# IPSv2_0.net
KiCad netlist of a schematic drawn in EAGLE
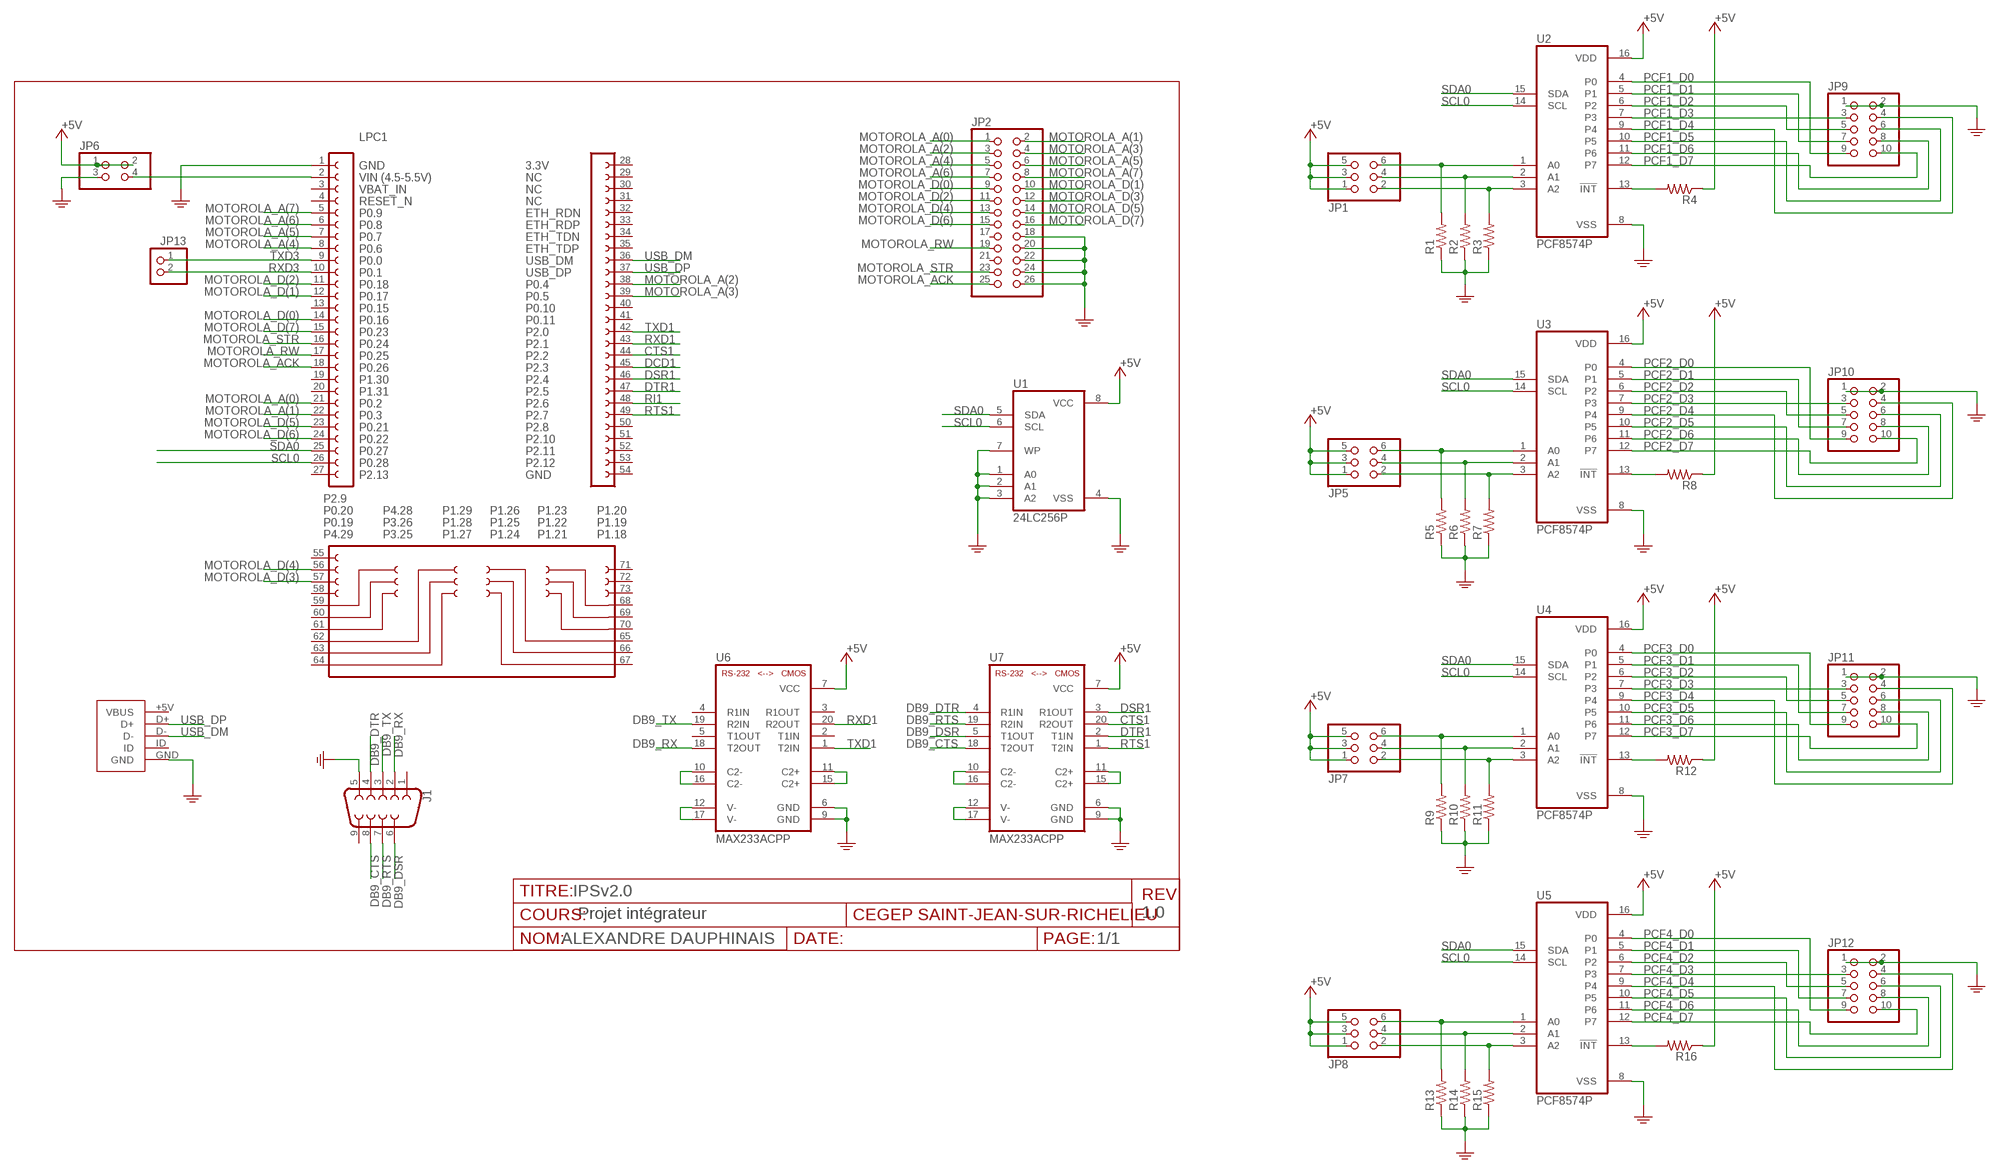
[diagram p0: schematic, sheet 1]

(export (version "E")
  (design (tool "Eeschema 10.0.6"))
  (components
    (comp (ref "J1")
      (value "DB9FEMALE")
      (footprint "eagle-import:DB9")
      (libsource (lib "eagle-import") (part "DB9FEMALE"))
    )
    (comp (ref "JP1")
      (value "PINHD-2X3")
      (footprint "eagle-import:2X03")
      (libsource (lib "eagle-import") (part "PINHD-2X3"))
    )
    (comp (ref "JP2")
      (value "PINHD-2X13")
      (footprint "eagle-import:2X13")
      (libsource (lib "eagle-import") (part "PINHD-2X13"))
    )
    (comp (ref "JP5")
      (value "PINHD-2X3")
      (footprint "eagle-import:2X03")
      (libsource (lib "eagle-import") (part "PINHD-2X3"))
    )
    (comp (ref "JP6")
      (value "PINHD-2X2")
      (footprint "eagle-import:2X02")
      (libsource (lib "eagle-import") (part "PINHD-2X2"))
    )
    (comp (ref "JP7")
      (value "PINHD-2X3")
      (footprint "eagle-import:2X03")
      (libsource (lib "eagle-import") (part "PINHD-2X3"))
    )
    (comp (ref "JP8")
      (value "PINHD-2X3")
      (footprint "eagle-import:2X03")
      (libsource (lib "eagle-import") (part "PINHD-2X3"))
    )
    (comp (ref "JP9")
      (value "PINHD-2X5")
      (footprint "eagle-import:2X05")
      (libsource (lib "eagle-import") (part "PINHD-2X5"))
    )
    (comp (ref "JP10")
      (value "PINHD-2X5")
      (footprint "eagle-import:2X05")
      (libsource (lib "eagle-import") (part "PINHD-2X5"))
    )
    (comp (ref "JP11")
      (value "PINHD-2X5")
      (footprint "eagle-import:2X05")
      (libsource (lib "eagle-import") (part "PINHD-2X5"))
    )
    (comp (ref "JP12")
      (value "PINHD-2X5")
      (footprint "eagle-import:2X05")
      (libsource (lib "eagle-import") (part "PINHD-2X5"))
    )
    (comp (ref "JP13")
      (value "PINHD-1X2")
      (footprint "eagle-import:1X02")
      (libsource (lib "eagle-import") (part "PINHD-1X2"))
    )
    (comp (ref "LPC1")
      (value "LPCXPRESSO_LPC1769")
      (footprint "eagle-import:LPCXPRESSO_LPC1769")
      (libsource (lib "eagle-import") (part "LPCXPRESSO_LPC1769"))
    )
    (comp (ref "R1")
      (value "R-US_M1206")
      (footprint "eagle-import:M1206")
      (libsource (lib "eagle-import") (part "R-US_M1206"))
    )
    (comp (ref "R2")
      (value "R-US_M1206")
      (footprint "eagle-import:M1206")
      (libsource (lib "eagle-import") (part "R-US_M1206"))
    )
    (comp (ref "R3")
      (value "R-US_M1206")
      (footprint "eagle-import:M1206")
      (libsource (lib "eagle-import") (part "R-US_M1206"))
    )
    (comp (ref "R4")
      (value "R-US_M1206")
      (footprint "eagle-import:M1206")
      (libsource (lib "eagle-import") (part "R-US_M1206"))
    )
    (comp (ref "R5")
      (value "R-US_M1206")
      (footprint "eagle-import:M1206")
      (libsource (lib "eagle-import") (part "R-US_M1206"))
    )
    (comp (ref "R6")
      (value "R-US_M1206")
      (footprint "eagle-import:M1206")
      (libsource (lib "eagle-import") (part "R-US_M1206"))
    )
    (comp (ref "R7")
      (value "R-US_M1206")
      (footprint "eagle-import:M1206")
      (libsource (lib "eagle-import") (part "R-US_M1206"))
    )
    (comp (ref "R8")
      (value "R-US_M1206")
      (footprint "eagle-import:M1206")
      (libsource (lib "eagle-import") (part "R-US_M1206"))
    )
    (comp (ref "R9")
      (value "R-US_M1206")
      (footprint "eagle-import:M1206")
      (libsource (lib "eagle-import") (part "R-US_M1206"))
    )
    (comp (ref "R10")
      (value "R-US_M1206")
      (footprint "eagle-import:M1206")
      (libsource (lib "eagle-import") (part "R-US_M1206"))
    )
    (comp (ref "R11")
      (value "R-US_M1206")
      (footprint "eagle-import:M1206")
      (libsource (lib "eagle-import") (part "R-US_M1206"))
    )
    (comp (ref "R12")
      (value "R-US_M1206")
      (footprint "eagle-import:M1206")
      (libsource (lib "eagle-import") (part "R-US_M1206"))
    )
    (comp (ref "R13")
      (value "R-US_M1206")
      (footprint "eagle-import:M1206")
      (libsource (lib "eagle-import") (part "R-US_M1206"))
    )
    (comp (ref "R14")
      (value "R-US_M1206")
      (footprint "eagle-import:M1206")
      (libsource (lib "eagle-import") (part "R-US_M1206"))
    )
    (comp (ref "R15")
      (value "R-US_M1206")
      (footprint "eagle-import:M1206")
      (libsource (lib "eagle-import") (part "R-US_M1206"))
    )
    (comp (ref "R16")
      (value "R-US_M1206")
      (footprint "eagle-import:M1206")
      (libsource (lib "eagle-import") (part "R-US_M1206"))
    )
    (comp (ref "U$2")
      (value "USB-MICRO-BREAKOUT")
      (footprint "eagle-import:USB-MICRO-BREAKOUT")
      (libsource (lib "eagle-import") (part "USB-MICRO-BREAKOUT"))
    )
    (comp (ref "U1")
      (value "24LC256P")
      (footprint "eagle-import:DIP08")
      (libsource (lib "eagle-import") (part "24LC256P"))
    )
    (comp (ref "U2")
      (value "PCF8574P")
      (footprint "eagle-import:DIP16")
      (libsource (lib "eagle-import") (part "PCF8574P"))
    )
    (comp (ref "U3")
      (value "PCF8574P")
      (footprint "eagle-import:DIP16")
      (libsource (lib "eagle-import") (part "PCF8574P"))
    )
    (comp (ref "U4")
      (value "PCF8574P")
      (footprint "eagle-import:DIP16")
      (libsource (lib "eagle-import") (part "PCF8574P"))
    )
    (comp (ref "U5")
      (value "PCF8574P")
      (footprint "eagle-import:DIP16")
      (libsource (lib "eagle-import") (part "PCF8574P"))
    )
    (comp (ref "U6")
      (value "MAX233ACPP")
      (footprint "eagle-import:DIP20")
      (libsource (lib "eagle-import") (part "MAX233ACPP"))
    )
    (comp (ref "U7")
      (value "MAX233ACPP")
      (footprint "eagle-import:DIP20")
      (libsource (lib "eagle-import") (part "MAX233ACPP"))
    )
  )
  (nets
    (net (code "1") (name "+5V") (class "Default")
      (node (ref "JP1") (pin "1") (pinfunction "1_1") (pintype "passive"))
      (node (ref "JP1") (pin "3") (pinfunction "3_3") (pintype "passive"))
      (node (ref "JP1") (pin "5") (pinfunction "5_5") (pintype "passive"))
      (node (ref "JP5") (pin "1") (pinfunction "1_1") (pintype "passive"))
      (node (ref "JP5") (pin "3") (pinfunction "3_3") (pintype "passive"))
      (node (ref "JP5") (pin "5") (pinfunction "5_5") (pintype "passive"))
      (node (ref "JP6") (pin "1") (pinfunction "1_1") (pintype "passive"))
      (node (ref "JP6") (pin "2") (pinfunction "2_2") (pintype "passive"))
      (node (ref "JP7") (pin "1") (pinfunction "1_1") (pintype "passive"))
      (node (ref "JP7") (pin "3") (pinfunction "3_3") (pintype "passive"))
      (node (ref "JP7") (pin "5") (pinfunction "5_5") (pintype "passive"))
      (node (ref "JP8") (pin "1") (pinfunction "1_1") (pintype "passive"))
      (node (ref "JP8") (pin "3") (pinfunction "3_3") (pintype "passive"))
      (node (ref "JP8") (pin "5") (pinfunction "5_5") (pintype "passive"))
      (node (ref "R12") (pin "1") (pinfunction "1_1") (pintype "passive"))
      (node (ref "R16") (pin "1") (pinfunction "1_1") (pintype "passive"))
      (node (ref "R4") (pin "1") (pinfunction "1_1") (pintype "passive"))
      (node (ref "R8") (pin "1") (pinfunction "1_1") (pintype "passive"))
      (node (ref "U1") (pin "8") (pinfunction "VCC_8") (pintype "power_in"))
      (node (ref "U2") (pin "16") (pinfunction "VDD_16") (pintype "power_in"))
      (node (ref "U3") (pin "16") (pinfunction "VDD_16") (pintype "power_in"))
      (node (ref "U4") (pin "16") (pinfunction "VDD_16") (pintype "power_in"))
      (node (ref "U5") (pin "16") (pinfunction "VDD_16") (pintype "power_in"))
      (node (ref "U6") (pin "7") (pinfunction "VCC_7") (pintype "power_in"))
      (node (ref "U7") (pin "7") (pinfunction "VCC_7") (pintype "power_in"))
    )
    (net (code "2") (name "/CTS1") (class "Default")
      (node (ref "LPC1") (pin "44") (pinfunction "44_44") (pintype "passive"))
      (node (ref "U7") (pin "20") (pinfunction "R2OUT_20") (pintype "output"))
    )
    (net (code "3") (name "/DB9_CTS") (class "Default")
      (node (ref "J1") (pin "8") (pinfunction "8_8") (pintype "passive"))
      (node (ref "U7") (pin "18") (pinfunction "T2OUT_18") (pintype "output"))
    )
    (net (code "4") (name "/DB9_DSR") (class "Default")
      (node (ref "J1") (pin "6") (pinfunction "6_6") (pintype "passive"))
      (node (ref "U7") (pin "5") (pinfunction "T1OUT_5") (pintype "output"))
    )
    (net (code "5") (name "/DB9_DTR") (class "Default")
      (node (ref "J1") (pin "4") (pinfunction "4_4") (pintype "passive"))
      (node (ref "U7") (pin "4") (pinfunction "R1IN_4") (pintype "input"))
    )
    (net (code "6") (name "/DB9_RTS") (class "Default")
      (node (ref "J1") (pin "7") (pinfunction "7_7") (pintype "passive"))
      (node (ref "U7") (pin "19") (pinfunction "R2IN_19") (pintype "input"))
    )
    (net (code "7") (name "/DB9_RX") (class "Default")
      (node (ref "J1") (pin "2") (pinfunction "2_2") (pintype "passive"))
      (node (ref "U6") (pin "18") (pinfunction "T2OUT_18") (pintype "output"))
    )
    (net (code "8") (name "/DB9_TX") (class "Default")
      (node (ref "J1") (pin "3") (pinfunction "3_3") (pintype "passive"))
      (node (ref "U6") (pin "19") (pinfunction "R2IN_19") (pintype "input"))
    )
    (net (code "9") (name "/DCD1") (class "Default")
      (node (ref "LPC1") (pin "45") (pinfunction "45_45") (pintype "passive"))
    )
    (net (code "10") (name "/DSR1") (class "Default")
      (node (ref "LPC1") (pin "46") (pinfunction "46_46") (pintype "passive"))
      (node (ref "U7") (pin "3") (pinfunction "R1OUT_3") (pintype "output"))
    )
    (net (code "11") (name "/DTR1") (class "Default")
      (node (ref "LPC1") (pin "47") (pinfunction "47_47") (pintype "passive"))
      (node (ref "U7") (pin "2") (pinfunction "T1IN_2") (pintype "input"))
    )
    (net (code "12") (name "/MOTOROLA_A(0)") (class "Default")
      (node (ref "JP2") (pin "1") (pinfunction "1_1") (pintype "passive"))
      (node (ref "LPC1") (pin "21") (pinfunction "21_21") (pintype "passive"))
    )
    (net (code "13") (name "/MOTOROLA_A(1)") (class "Default")
      (node (ref "JP2") (pin "2") (pinfunction "2_2") (pintype "passive"))
      (node (ref "LPC1") (pin "22") (pinfunction "22_22") (pintype "passive"))
    )
    (net (code "14") (name "/MOTOROLA_A(2)") (class "Default")
      (node (ref "JP2") (pin "3") (pinfunction "3_3") (pintype "passive"))
      (node (ref "LPC1") (pin "38") (pinfunction "38_38") (pintype "passive"))
    )
    (net (code "15") (name "/MOTOROLA_A(3)") (class "Default")
      (node (ref "JP2") (pin "4") (pinfunction "4_4") (pintype "passive"))
      (node (ref "LPC1") (pin "39") (pinfunction "39_39") (pintype "passive"))
    )
    (net (code "16") (name "/MOTOROLA_A(4)") (class "Default")
      (node (ref "JP2") (pin "5") (pinfunction "5_5") (pintype "passive"))
      (node (ref "LPC1") (pin "8") (pinfunction "8_8") (pintype "passive"))
    )
    (net (code "17") (name "/MOTOROLA_A(5)") (class "Default")
      (node (ref "JP2") (pin "6") (pinfunction "6_6") (pintype "passive"))
      (node (ref "LPC1") (pin "7") (pinfunction "7_7") (pintype "passive"))
    )
    (net (code "18") (name "/MOTOROLA_A(6)") (class "Default")
      (node (ref "JP2") (pin "7") (pinfunction "7_7") (pintype "passive"))
      (node (ref "LPC1") (pin "6") (pinfunction "6_6") (pintype "passive"))
    )
    (net (code "19") (name "/MOTOROLA_A(7)") (class "Default")
      (node (ref "JP2") (pin "8") (pinfunction "8_8") (pintype "passive"))
      (node (ref "LPC1") (pin "5") (pinfunction "5_5") (pintype "passive"))
    )
    (net (code "20") (name "/MOTOROLA_ACK") (class "Default")
      (node (ref "JP2") (pin "25") (pinfunction "25_25") (pintype "passive"))
      (node (ref "LPC1") (pin "18") (pinfunction "18_18") (pintype "passive"))
    )
    (net (code "21") (name "/MOTOROLA_D(0)") (class "Default")
      (node (ref "JP2") (pin "9") (pinfunction "9_9") (pintype "passive"))
      (node (ref "LPC1") (pin "14") (pinfunction "14_14") (pintype "passive"))
    )
    (net (code "22") (name "/MOTOROLA_D(1)") (class "Default")
      (node (ref "JP2") (pin "10") (pinfunction "10_10") (pintype "passive"))
      (node (ref "LPC1") (pin "12") (pinfunction "12_12") (pintype "passive"))
    )
    (net (code "23") (name "/MOTOROLA_D(2)") (class "Default")
      (node (ref "JP2") (pin "11") (pinfunction "11_11") (pintype "passive"))
      (node (ref "LPC1") (pin "11") (pinfunction "11_11") (pintype "passive"))
    )
    (net (code "24") (name "/MOTOROLA_D(3)") (class "Default")
      (node (ref "JP2") (pin "12") (pinfunction "12_12") (pintype "passive"))
      (node (ref "LPC1") (pin "57") (pinfunction "57_57") (pintype "passive"))
    )
    (net (code "25") (name "/MOTOROLA_D(4)") (class "Default")
      (node (ref "JP2") (pin "13") (pinfunction "13_13") (pintype "passive"))
      (node (ref "LPC1") (pin "56") (pinfunction "56_56") (pintype "passive"))
    )
    (net (code "26") (name "/MOTOROLA_D(5)") (class "Default")
      (node (ref "JP2") (pin "14") (pinfunction "14_14") (pintype "passive"))
      (node (ref "LPC1") (pin "23") (pinfunction "23_23") (pintype "passive"))
    )
    (net (code "27") (name "/MOTOROLA_D(6)") (class "Default")
      (node (ref "JP2") (pin "15") (pinfunction "15_15") (pintype "passive"))
      (node (ref "LPC1") (pin "24") (pinfunction "24_24") (pintype "passive"))
    )
    (net (code "28") (name "/MOTOROLA_D(7)") (class "Default")
      (node (ref "JP2") (pin "16") (pinfunction "16_16") (pintype "passive"))
      (node (ref "LPC1") (pin "15") (pinfunction "15_15") (pintype "passive"))
    )
    (net (code "29") (name "/MOTOROLA_RW") (class "Default")
      (node (ref "JP2") (pin "19") (pinfunction "19_19") (pintype "passive"))
      (node (ref "LPC1") (pin "17") (pinfunction "17_17") (pintype "passive"))
    )
    (net (code "30") (name "/MOTOROLA_STR") (class "Default")
      (node (ref "JP2") (pin "23") (pinfunction "23_23") (pintype "passive"))
      (node (ref "LPC1") (pin "16") (pinfunction "16_16") (pintype "passive"))
    )
    (net (code "31") (name "/PCF1_D0") (class "Default")
      (node (ref "JP9") (pin "9") (pinfunction "9_9") (pintype "passive"))
      (node (ref "U2") (pin "4") (pinfunction "P0_4") (pintype "bidirectional"))
    )
    (net (code "32") (name "/PCF1_D1") (class "Default")
      (node (ref "JP9") (pin "7") (pinfunction "7_7") (pintype "passive"))
      (node (ref "U2") (pin "5") (pinfunction "P1_5") (pintype "bidirectional"))
    )
    (net (code "33") (name "/PCF1_D2") (class "Default")
      (node (ref "JP9") (pin "5") (pinfunction "5_5") (pintype "passive"))
      (node (ref "U2") (pin "6") (pinfunction "P2_6") (pintype "bidirectional"))
    )
    (net (code "34") (name "/PCF1_D3") (class "Default")
      (node (ref "JP9") (pin "3") (pinfunction "3_3") (pintype "passive"))
      (node (ref "U2") (pin "7") (pinfunction "P3_7") (pintype "bidirectional"))
    )
    (net (code "35") (name "/PCF1_D4") (class "Default")
      (node (ref "JP9") (pin "4") (pinfunction "4_4") (pintype "passive"))
      (node (ref "U2") (pin "9") (pinfunction "P4_9") (pintype "bidirectional"))
    )
    (net (code "36") (name "/PCF1_D5") (class "Default")
      (node (ref "JP9") (pin "6") (pinfunction "6_6") (pintype "passive"))
      (node (ref "U2") (pin "10") (pinfunction "P5_10") (pintype "bidirectional"))
    )
    (net (code "37") (name "/PCF1_D6") (class "Default")
      (node (ref "JP9") (pin "8") (pinfunction "8_8") (pintype "passive"))
      (node (ref "U2") (pin "11") (pinfunction "P6_11") (pintype "bidirectional"))
    )
    (net (code "38") (name "/PCF1_D7") (class "Default")
      (node (ref "JP9") (pin "10") (pinfunction "10_10") (pintype "passive"))
      (node (ref "U2") (pin "12") (pinfunction "P7_12") (pintype "bidirectional"))
    )
    (net (code "39") (name "/PCF2_D0") (class "Default")
      (node (ref "JP10") (pin "9") (pinfunction "9_9") (pintype "passive"))
      (node (ref "U3") (pin "4") (pinfunction "P0_4") (pintype "bidirectional"))
    )
    (net (code "40") (name "/PCF2_D1") (class "Default")
      (node (ref "JP10") (pin "7") (pinfunction "7_7") (pintype "passive"))
      (node (ref "U3") (pin "5") (pinfunction "P1_5") (pintype "bidirectional"))
    )
    (net (code "41") (name "/PCF2_D2") (class "Default")
      (node (ref "JP10") (pin "5") (pinfunction "5_5") (pintype "passive"))
      (node (ref "U3") (pin "6") (pinfunction "P2_6") (pintype "bidirectional"))
    )
    (net (code "42") (name "/PCF2_D3") (class "Default")
      (node (ref "JP10") (pin "3") (pinfunction "3_3") (pintype "passive"))
      (node (ref "U3") (pin "7") (pinfunction "P3_7") (pintype "bidirectional"))
    )
    (net (code "43") (name "/PCF2_D4") (class "Default")
      (node (ref "JP10") (pin "4") (pinfunction "4_4") (pintype "passive"))
      (node (ref "U3") (pin "9") (pinfunction "P4_9") (pintype "bidirectional"))
    )
    (net (code "44") (name "/PCF2_D5") (class "Default")
      (node (ref "JP10") (pin "6") (pinfunction "6_6") (pintype "passive"))
      (node (ref "U3") (pin "10") (pinfunction "P5_10") (pintype "bidirectional"))
    )
    (net (code "45") (name "/PCF2_D6") (class "Default")
      (node (ref "JP10") (pin "8") (pinfunction "8_8") (pintype "passive"))
      (node (ref "U3") (pin "11") (pinfunction "P6_11") (pintype "bidirectional"))
    )
    (net (code "46") (name "/PCF2_D7") (class "Default")
      (node (ref "JP10") (pin "10") (pinfunction "10_10") (pintype "passive"))
      (node (ref "U3") (pin "12") (pinfunction "P7_12") (pintype "bidirectional"))
    )
    (net (code "47") (name "/PCF3_D0") (class "Default")
      (node (ref "JP11") (pin "9") (pinfunction "9_9") (pintype "passive"))
      (node (ref "U4") (pin "4") (pinfunction "P0_4") (pintype "bidirectional"))
    )
    (net (code "48") (name "/PCF3_D1") (class "Default")
      (node (ref "JP11") (pin "7") (pinfunction "7_7") (pintype "passive"))
      (node (ref "U4") (pin "5") (pinfunction "P1_5") (pintype "bidirectional"))
    )
    (net (code "49") (name "/PCF3_D2") (class "Default")
      (node (ref "JP11") (pin "5") (pinfunction "5_5") (pintype "passive"))
      (node (ref "U4") (pin "6") (pinfunction "P2_6") (pintype "bidirectional"))
    )
    (net (code "50") (name "/PCF3_D3") (class "Default")
      (node (ref "JP11") (pin "3") (pinfunction "3_3") (pintype "passive"))
      (node (ref "U4") (pin "7") (pinfunction "P3_7") (pintype "bidirectional"))
    )
    (net (code "51") (name "/PCF3_D4") (class "Default")
      (node (ref "JP11") (pin "4") (pinfunction "4_4") (pintype "passive"))
      (node (ref "U4") (pin "9") (pinfunction "P4_9") (pintype "bidirectional"))
    )
    (net (code "52") (name "/PCF3_D5") (class "Default")
      (node (ref "JP11") (pin "6") (pinfunction "6_6") (pintype "passive"))
      (node (ref "U4") (pin "10") (pinfunction "P5_10") (pintype "bidirectional"))
    )
    (net (code "53") (name "/PCF3_D6") (class "Default")
      (node (ref "JP11") (pin "8") (pinfunction "8_8") (pintype "passive"))
      (node (ref "U4") (pin "11") (pinfunction "P6_11") (pintype "bidirectional"))
    )
    (net (code "54") (name "/PCF3_D7") (class "Default")
      (node (ref "JP11") (pin "10") (pinfunction "10_10") (pintype "passive"))
      (node (ref "U4") (pin "12") (pinfunction "P7_12") (pintype "bidirectional"))
    )
    (net (code "55") (name "/PCF4_D0") (class "Default")
      (node (ref "JP12") (pin "9") (pinfunction "9_9") (pintype "passive"))
      (node (ref "U5") (pin "4") (pinfunction "P0_4") (pintype "bidirectional"))
    )
    (net (code "56") (name "/PCF4_D1") (class "Default")
      (node (ref "JP12") (pin "7") (pinfunction "7_7") (pintype "passive"))
      (node (ref "U5") (pin "5") (pinfunction "P1_5") (pintype "bidirectional"))
    )
    (net (code "57") (name "/PCF4_D2") (class "Default")
      (node (ref "JP12") (pin "5") (pinfunction "5_5") (pintype "passive"))
      (node (ref "U5") (pin "6") (pinfunction "P2_6") (pintype "bidirectional"))
    )
    (net (code "58") (name "/PCF4_D3") (class "Default")
      (node (ref "JP12") (pin "3") (pinfunction "3_3") (pintype "passive"))
      (node (ref "U5") (pin "7") (pinfunction "P3_7") (pintype "bidirectional"))
    )
    (net (code "59") (name "/PCF4_D4") (class "Default")
      (node (ref "JP12") (pin "4") (pinfunction "4_4") (pintype "passive"))
      (node (ref "U5") (pin "9") (pinfunction "P4_9") (pintype "bidirectional"))
    )
    (net (code "60") (name "/PCF4_D5") (class "Default")
      (node (ref "JP12") (pin "6") (pinfunction "6_6") (pintype "passive"))
      (node (ref "U5") (pin "10") (pinfunction "P5_10") (pintype "bidirectional"))
    )
    (net (code "61") (name "/PCF4_D6") (class "Default")
      (node (ref "JP12") (pin "8") (pinfunction "8_8") (pintype "passive"))
      (node (ref "U5") (pin "11") (pinfunction "P6_11") (pintype "bidirectional"))
    )
    (net (code "62") (name "/PCF4_D7") (class "Default")
      (node (ref "JP12") (pin "10") (pinfunction "10_10") (pintype "passive"))
      (node (ref "U5") (pin "12") (pinfunction "P7_12") (pintype "bidirectional"))
    )
    (net (code "63") (name "/RI1") (class "Default")
      (node (ref "LPC1") (pin "48") (pinfunction "48_48") (pintype "passive"))
    )
    (net (code "64") (name "/RTS1") (class "Default")
      (node (ref "LPC1") (pin "49") (pinfunction "49_49") (pintype "passive"))
      (node (ref "U7") (pin "1") (pinfunction "T2IN_1") (pintype "input"))
    )
    (net (code "65") (name "/RXD1") (class "Default")
      (node (ref "LPC1") (pin "43") (pinfunction "43_43") (pintype "passive"))
      (node (ref "U6") (pin "20") (pinfunction "R2OUT_20") (pintype "output"))
    )
    (net (code "66") (name "/RXD3") (class "Default")
      (node (ref "JP13") (pin "2") (pinfunction "2_2") (pintype "passive"))
      (node (ref "LPC1") (pin "10") (pinfunction "10_10") (pintype "passive"))
    )
    (net (code "67") (name "/SCL0") (class "Default")
      (node (ref "LPC1") (pin "26") (pinfunction "26_26") (pintype "passive"))
      (node (ref "U1") (pin "6") (pinfunction "SCL_6") (pintype "input"))
      (node (ref "U2") (pin "14") (pinfunction "SCL_14") (pintype "input"))
      (node (ref "U3") (pin "14") (pinfunction "SCL_14") (pintype "input"))
      (node (ref "U4") (pin "14") (pinfunction "SCL_14") (pintype "input"))
      (node (ref "U5") (pin "14") (pinfunction "SCL_14") (pintype "input"))
    )
    (net (code "68") (name "/SDA0") (class "Default")
      (node (ref "LPC1") (pin "25") (pinfunction "25_25") (pintype "passive"))
      (node (ref "U1") (pin "5") (pinfunction "SDA_5") (pintype "bidirectional"))
      (node (ref "U2") (pin "15") (pinfunction "SDA_15") (pintype "bidirectional"))
      (node (ref "U3") (pin "15") (pinfunction "SDA_15") (pintype "bidirectional"))
      (node (ref "U4") (pin "15") (pinfunction "SDA_15") (pintype "bidirectional"))
      (node (ref "U5") (pin "15") (pinfunction "SDA_15") (pintype "bidirectional"))
    )
    (net (code "69") (name "/TXD1") (class "Default")
      (node (ref "LPC1") (pin "42") (pinfunction "42_42") (pintype "passive"))
      (node (ref "U6") (pin "1") (pinfunction "T2IN_1") (pintype "input"))
    )
    (net (code "70") (name "/TXD3") (class "Default")
      (node (ref "JP13") (pin "1") (pinfunction "1_1") (pintype "passive"))
      (node (ref "LPC1") (pin "9") (pinfunction "9_9") (pintype "passive"))
    )
    (net (code "71") (name "/USB_DM") (class "Default")
      (node (ref "LPC1") (pin "36") (pinfunction "36_36") (pintype "passive"))
      (node (ref "U$2") (pin "D-") (pinfunction "D-_D-") (pintype "bidirectional"))
    )
    (net (code "72") (name "/USB_DP") (class "Default")
      (node (ref "LPC1") (pin "37") (pinfunction "37_37") (pintype "passive"))
      (node (ref "U$2") (pin "D+") (pinfunction "D+_D+") (pintype "bidirectional"))
    )
    (net (code "73") (name "/VBUS") (class "Default")
      (node (ref "U$2") (pin "+5V") (pinfunction "VBUS_+5V") (pintype "power_in"))
    )
    (net (code "74") (name "GND") (class "Default")
      (node (ref "J1") (pin "5") (pinfunction "5_5") (pintype "passive"))
      (node (ref "JP10") (pin "1") (pinfunction "1_1") (pintype "passive"))
      (node (ref "JP10") (pin "2") (pinfunction "2_2") (pintype "passive"))
      (node (ref "JP11") (pin "1") (pinfunction "1_1") (pintype "passive"))
      (node (ref "JP11") (pin "2") (pinfunction "2_2") (pintype "passive"))
      (node (ref "JP12") (pin "1") (pinfunction "1_1") (pintype "passive"))
      (node (ref "JP12") (pin "2") (pinfunction "2_2") (pintype "passive"))
      (node (ref "JP2") (pin "18") (pinfunction "18_18") (pintype "passive"))
      (node (ref "JP2") (pin "20") (pinfunction "20_20") (pintype "passive"))
      (node (ref "JP2") (pin "22") (pinfunction "22_22") (pintype "passive"))
      (node (ref "JP2") (pin "24") (pinfunction "24_24") (pintype "passive"))
      (node (ref "JP2") (pin "26") (pinfunction "26_26") (pintype "passive"))
      (node (ref "JP6") (pin "3") (pinfunction "3_3") (pintype "passive"))
      (node (ref "JP9") (pin "1") (pinfunction "1_1") (pintype "passive"))
      (node (ref "JP9") (pin "2") (pinfunction "2_2") (pintype "passive"))
      (node (ref "LPC1") (pin "1") (pinfunction "1_1") (pintype "passive"))
      (node (ref "R1") (pin "1") (pinfunction "1_1") (pintype "passive"))
      (node (ref "R10") (pin "1") (pinfunction "1_1") (pintype "passive"))
      (node (ref "R11") (pin "1") (pinfunction "1_1") (pintype "passive"))
      (node (ref "R13") (pin "1") (pinfunction "1_1") (pintype "passive"))
      (node (ref "R14") (pin "1") (pinfunction "1_1") (pintype "passive"))
      (node (ref "R15") (pin "1") (pinfunction "1_1") (pintype "passive"))
      (node (ref "R2") (pin "1") (pinfunction "1_1") (pintype "passive"))
      (node (ref "R3") (pin "1") (pinfunction "1_1") (pintype "passive"))
      (node (ref "R5") (pin "1") (pinfunction "1_1") (pintype "passive"))
      (node (ref "R6") (pin "1") (pinfunction "1_1") (pintype "passive"))
      (node (ref "R7") (pin "1") (pinfunction "1_1") (pintype "passive"))
      (node (ref "R9") (pin "1") (pinfunction "1_1") (pintype "passive"))
      (node (ref "U$2") (pin "GND") (pinfunction "GND_GND") (pintype "power_in"))
      (node (ref "U1") (pin "1") (pinfunction "A0_1") (pintype "input"))
      (node (ref "U1") (pin "2") (pinfunction "A1_2") (pintype "input"))
      (node (ref "U1") (pin "3") (pinfunction "A2_3") (pintype "input"))
      (node (ref "U1") (pin "4") (pinfunction "VSS_4") (pintype "power_in"))
      (node (ref "U1") (pin "7") (pinfunction "WP_7") (pintype "input"))
      (node (ref "U2") (pin "8") (pinfunction "VSS_8") (pintype "power_in"))
      (node (ref "U3") (pin "8") (pinfunction "VSS_8") (pintype "power_in"))
      (node (ref "U4") (pin "8") (pinfunction "VSS_8") (pintype "power_in"))
      (node (ref "U5") (pin "8") (pinfunction "VSS_8") (pintype "power_in"))
      (node (ref "U6") (pin "6") (pinfunction "GND_6") (pintype "power_in"))
      (node (ref "U6") (pin "9") (pinfunction "GND_9") (pintype "power_in"))
      (node (ref "U7") (pin "6") (pinfunction "GND_6") (pintype "power_in"))
      (node (ref "U7") (pin "9") (pinfunction "GND_9") (pintype "power_in"))
    )
    (net (code "75") (name "Net-(JP6-Pad4)") (class "Default")
      (node (ref "JP6") (pin "4") (pinfunction "4_4") (pintype "passive"))
      (node (ref "LPC1") (pin "2") (pinfunction "2_2") (pintype "passive"))
    )
    (net (code "76") (name "Net-(U2-A0)") (class "Default")
      (node (ref "JP1") (pin "6") (pinfunction "6_6") (pintype "passive"))
      (node (ref "R1") (pin "2") (pinfunction "2_2") (pintype "passive"))
      (node (ref "U2") (pin "1") (pinfunction "A0_1") (pintype "input"))
    )
    (net (code "77") (name "Net-(U2-A1)") (class "Default")
      (node (ref "JP1") (pin "4") (pinfunction "4_4") (pintype "passive"))
      (node (ref "R2") (pin "2") (pinfunction "2_2") (pintype "passive"))
      (node (ref "U2") (pin "2") (pinfunction "A1_2") (pintype "input"))
    )
    (net (code "78") (name "Net-(U2-A2)") (class "Default")
      (node (ref "JP1") (pin "2") (pinfunction "2_2") (pintype "passive"))
      (node (ref "R3") (pin "2") (pinfunction "2_2") (pintype "passive"))
      (node (ref "U2") (pin "3") (pinfunction "A2_3") (pintype "input"))
    )
    (net (code "79") (name "Net-(U2-~{INT})") (class "Default")
      (node (ref "R4") (pin "2") (pinfunction "2_2") (pintype "passive"))
      (node (ref "U2") (pin "13") (pinfunction "~{INT}_13") (pintype "output"))
    )
    (net (code "80") (name "Net-(U3-A0)") (class "Default")
      (node (ref "JP5") (pin "6") (pinfunction "6_6") (pintype "passive"))
      (node (ref "R5") (pin "2") (pinfunction "2_2") (pintype "passive"))
      (node (ref "U3") (pin "1") (pinfunction "A0_1") (pintype "input"))
    )
    (net (code "81") (name "Net-(U3-A1)") (class "Default")
      (node (ref "JP5") (pin "4") (pinfunction "4_4") (pintype "passive"))
      (node (ref "R6") (pin "2") (pinfunction "2_2") (pintype "passive"))
      (node (ref "U3") (pin "2") (pinfunction "A1_2") (pintype "input"))
    )
    (net (code "82") (name "Net-(U3-A2)") (class "Default")
      (node (ref "JP5") (pin "2") (pinfunction "2_2") (pintype "passive"))
      (node (ref "R7") (pin "2") (pinfunction "2_2") (pintype "passive"))
      (node (ref "U3") (pin "3") (pinfunction "A2_3") (pintype "input"))
    )
    (net (code "83") (name "Net-(U3-~{INT})") (class "Default")
      (node (ref "R8") (pin "2") (pinfunction "2_2") (pintype "passive"))
      (node (ref "U3") (pin "13") (pinfunction "~{INT}_13") (pintype "output"))
    )
    (net (code "84") (name "Net-(U4-A0)") (class "Default")
      (node (ref "JP7") (pin "6") (pinfunction "6_6") (pintype "passive"))
      (node (ref "R9") (pin "2") (pinfunction "2_2") (pintype "passive"))
      (node (ref "U4") (pin "1") (pinfunction "A0_1") (pintype "input"))
    )
    (net (code "85") (name "Net-(U4-A1)") (class "Default")
      (node (ref "JP7") (pin "4") (pinfunction "4_4") (pintype "passive"))
      (node (ref "R10") (pin "2") (pinfunction "2_2") (pintype "passive"))
      (node (ref "U4") (pin "2") (pinfunction "A1_2") (pintype "input"))
    )
    (net (code "86") (name "Net-(U4-A2)") (class "Default")
      (node (ref "JP7") (pin "2") (pinfunction "2_2") (pintype "passive"))
      (node (ref "R11") (pin "2") (pinfunction "2_2") (pintype "passive"))
      (node (ref "U4") (pin "3") (pinfunction "A2_3") (pintype "input"))
    )
    (net (code "87") (name "Net-(U4-~{INT})") (class "Default")
      (node (ref "R12") (pin "2") (pinfunction "2_2") (pintype "passive"))
      (node (ref "U4") (pin "13") (pinfunction "~{INT}_13") (pintype "output"))
    )
    (net (code "88") (name "Net-(U5-A0)") (class "Default")
      (node (ref "JP8") (pin "6") (pinfunction "6_6") (pintype "passive"))
      (node (ref "R13") (pin "2") (pinfunction "2_2") (pintype "passive"))
      (node (ref "U5") (pin "1") (pinfunction "A0_1") (pintype "input"))
    )
    (net (code "89") (name "Net-(U5-A1)") (class "Default")
      (node (ref "JP8") (pin "4") (pinfunction "4_4") (pintype "passive"))
      (node (ref "R14") (pin "2") (pinfunction "2_2") (pintype "passive"))
      (node (ref "U5") (pin "2") (pinfunction "A1_2") (pintype "input"))
    )
    (net (code "90") (name "Net-(U5-A2)") (class "Default")
      (node (ref "JP8") (pin "2") (pinfunction "2_2") (pintype "passive"))
      (node (ref "R15") (pin "2") (pinfunction "2_2") (pintype "passive"))
      (node (ref "U5") (pin "3") (pinfunction "A2_3") (pintype "input"))
    )
    (net (code "91") (name "Net-(U5-~{INT})") (class "Default")
      (node (ref "R16") (pin "2") (pinfunction "2_2") (pintype "passive"))
      (node (ref "U5") (pin "13") (pinfunction "~{INT}_13") (pintype "output"))
    )
    (net (code "92") (name "Net-(U6-C2+-Pad11)") (class "Default")
      (node (ref "U6") (pin "11") (pinfunction "C2+_11") (pintype "passive"))
      (node (ref "U6") (pin "15") (pinfunction "C2+_15") (pintype "passive"))
    )
    (net (code "93") (name "Net-(U6-C2--Pad10)") (class "Default")
      (node (ref "U6") (pin "10") (pinfunction "C2-_10") (pintype "passive"))
      (node (ref "U6") (pin "16") (pinfunction "C2-_16") (pintype "passive"))
    )
    (net (code "94") (name "Net-(U6-V--Pad12)") (class "Default")
      (node (ref "U6") (pin "12") (pinfunction "V-_12") (pintype "passive"))
      (node (ref "U6") (pin "17") (pinfunction "V-_17") (pintype "passive"))
    )
    (net (code "95") (name "Net-(U7-C2+-Pad11)") (class "Default")
      (node (ref "U7") (pin "11") (pinfunction "C2+_11") (pintype "passive"))
      (node (ref "U7") (pin "15") (pinfunction "C2+_15") (pintype "passive"))
    )
    (net (code "96") (name "Net-(U7-C2--Pad10)") (class "Default")
      (node (ref "U7") (pin "10") (pinfunction "C2-_10") (pintype "passive"))
      (node (ref "U7") (pin "16") (pinfunction "C2-_16") (pintype "passive"))
    )
    (net (code "97") (name "Net-(U7-V--Pad12)") (class "Default")
      (node (ref "U7") (pin "12") (pinfunction "V-_12") (pintype "passive"))
      (node (ref "U7") (pin "17") (pinfunction "V-_17") (pintype "passive"))
    )
    (net (code "98") (name "unconnected-(J1-Pad1)") (class "Default")
      (node (ref "J1") (pin "1") (pinfunction "1_1") (pintype "passive"))
    )
    (net (code "99") (name "unconnected-(J1-Pad9)") (class "Default")
      (node (ref "J1") (pin "9") (pinfunction "9_9") (pintype "passive"))
    )
    (net (code "100") (name "unconnected-(JP2-Pad17)") (class "Default")
      (node (ref "JP2") (pin "17") (pinfunction "17_17") (pintype "passive"))
    )
    (net (code "101") (name "unconnected-(JP2-Pad21)") (class "Default")
      (node (ref "JP2") (pin "21") (pinfunction "21_21") (pintype "passive"))
    )
    (net (code "102") (name "unconnected-(LPC1-Pad3)") (class "Default")
      (node (ref "LPC1") (pin "3") (pinfunction "3_3") (pintype "passive"))
    )
    (net (code "103") (name "unconnected-(LPC1-Pad4)") (class "Default")
      (node (ref "LPC1") (pin "4") (pinfunction "4_4") (pintype "passive"))
    )
    (net (code "104") (name "unconnected-(LPC1-Pad13)") (class "Default")
      (node (ref "LPC1") (pin "13") (pinfunction "13_13") (pintype "passive"))
    )
    (net (code "105") (name "unconnected-(LPC1-Pad19)") (class "Default")
      (node (ref "LPC1") (pin "19") (pinfunction "19_19") (pintype "passive"))
    )
    (net (code "106") (name "unconnected-(LPC1-Pad20)") (class "Default")
      (node (ref "LPC1") (pin "20") (pinfunction "20_20") (pintype "passive"))
    )
    (net (code "107") (name "unconnected-(LPC1-Pad27)") (class "Default")
      (node (ref "LPC1") (pin "27") (pinfunction "27_27") (pintype "passive"))
    )
    (net (code "108") (name "unconnected-(LPC1-Pad28)") (class "Default")
      (node (ref "LPC1") (pin "28") (pinfunction "28_28") (pintype "passive"))
    )
    (net (code "109") (name "unconnected-(LPC1-Pad29)") (class "Default")
      (node (ref "LPC1") (pin "29") (pinfunction "29_29") (pintype "passive"))
    )
    (net (code "110") (name "unconnected-(LPC1-Pad30)") (class "Default")
      (node (ref "LPC1") (pin "30") (pinfunction "30_30") (pintype "passive"))
    )
    (net (code "111") (name "unconnected-(LPC1-Pad31)") (class "Default")
      (node (ref "LPC1") (pin "31") (pinfunction "31_31") (pintype "passive"))
    )
    (net (code "112") (name "unconnected-(LPC1-Pad32)") (class "Default")
      (node (ref "LPC1") (pin "32") (pinfunction "32_32") (pintype "passive"))
    )
    (net (code "113") (name "unconnected-(LPC1-Pad33)") (class "Default")
      (node (ref "LPC1") (pin "33") (pinfunction "33_33") (pintype "passive"))
    )
    (net (code "114") (name "unconnected-(LPC1-Pad34)") (class "Default")
      (node (ref "LPC1") (pin "34") (pinfunction "34_34") (pintype "passive"))
    )
    (net (code "115") (name "unconnected-(LPC1-Pad35)") (class "Default")
      (node (ref "LPC1") (pin "35") (pinfunction "35_35") (pintype "passive"))
    )
    (net (code "116") (name "unconnected-(LPC1-Pad40)") (class "Default")
      (node (ref "LPC1") (pin "40") (pinfunction "40_40") (pintype "passive"))
    )
    (net (code "117") (name "unconnected-(LPC1-Pad41)") (class "Default")
      (node (ref "LPC1") (pin "41") (pinfunction "41_41") (pintype "passive"))
    )
    (net (code "118") (name "unconnected-(LPC1-Pad50)") (class "Default")
      (node (ref "LPC1") (pin "50") (pinfunction "50_50") (pintype "passive"))
    )
    (net (code "119") (name "unconnected-(LPC1-Pad51)") (class "Default")
      (node (ref "LPC1") (pin "51") (pinfunction "51_51") (pintype "passive"))
    )
    (net (code "120") (name "unconnected-(LPC1-Pad52)") (class "Default")
      (node (ref "LPC1") (pin "52") (pinfunction "52_52") (pintype "passive"))
    )
    (net (code "121") (name "unconnected-(LPC1-Pad53)") (class "Default")
      (node (ref "LPC1") (pin "53") (pinfunction "53_53") (pintype "passive"))
    )
    (net (code "122") (name "unconnected-(LPC1-Pad54)") (class "Default")
      (node (ref "LPC1") (pin "54") (pinfunction "54_54") (pintype "passive"))
    )
    (net (code "123") (name "unconnected-(LPC1-Pad55)") (class "Default")
      (node (ref "LPC1") (pin "55") (pinfunction "55_55") (pintype "passive"))
    )
    (net (code "124") (name "unconnected-(LPC1-Pad58)") (class "Default")
      (node (ref "LPC1") (pin "58") (pinfunction "58_58") (pintype "passive"))
    )
    (net (code "125") (name "unconnected-(LPC1-Pad59)") (class "Default")
      (node (ref "LPC1") (pin "59") (pinfunction "59_59") (pintype "passive"))
    )
    (net (code "126") (name "unconnected-(LPC1-Pad60)") (class "Default")
      (node (ref "LPC1") (pin "60") (pinfunction "60_60") (pintype "passive"))
    )
    (net (code "127") (name "unconnected-(LPC1-Pad61)") (class "Default")
      (node (ref "LPC1") (pin "61") (pinfunction "61_61") (pintype "passive"))
    )
    (net (code "128") (name "unconnected-(LPC1-Pad62)") (class "Default")
      (node (ref "LPC1") (pin "62") (pinfunction "62_62") (pintype "passive"))
    )
    (net (code "129") (name "unconnected-(LPC1-Pad63)") (class "Default")
      (node (ref "LPC1") (pin "63") (pinfunction "63_63") (pintype "passive"))
    )
    (net (code "130") (name "unconnected-(LPC1-Pad64)") (class "Default")
      (node (ref "LPC1") (pin "64") (pinfunction "64_64") (pintype "passive"))
    )
    (net (code "131") (name "unconnected-(LPC1-Pad65)") (class "Default")
      (node (ref "LPC1") (pin "65") (pinfunction "65_65") (pintype "passive"))
    )
    (net (code "132") (name "unconnected-(LPC1-Pad66)") (class "Default")
      (node (ref "LPC1") (pin "66") (pinfunction "66_66") (pintype "passive"))
    )
    (net (code "133") (name "unconnected-(LPC1-Pad67)") (class "Default")
      (node (ref "LPC1") (pin "67") (pinfunction "67_67") (pintype "passive"))
    )
    (net (code "134") (name "unconnected-(LPC1-Pad68)") (class "Default")
      (node (ref "LPC1") (pin "68") (pinfunction "68_68") (pintype "passive"))
    )
    (net (code "135") (name "unconnected-(LPC1-Pad69)") (class "Default")
      (node (ref "LPC1") (pin "69") (pinfunction "69_69") (pintype "passive"))
    )
    (net (code "136") (name "unconnected-(LPC1-Pad70)") (class "Default")
      (node (ref "LPC1") (pin "70") (pinfunction "70_70") (pintype "passive"))
    )
    (net (code "137") (name "unconnected-(LPC1-Pad71)") (class "Default")
      (node (ref "LPC1") (pin "71") (pinfunction "71_71") (pintype "passive"))
    )
    (net (code "138") (name "unconnected-(LPC1-Pad72)") (class "Default")
      (node (ref "LPC1") (pin "72") (pinfunction "72_72") (pintype "passive"))
    )
    (net (code "139") (name "unconnected-(LPC1-Pad73)") (class "Default")
      (node (ref "LPC1") (pin "73") (pinfunction "73_73") (pintype "passive"))
    )
    (net (code "140") (name "unconnected-(U$2-PadID)") (class "Default")
      (node (ref "U$2") (pin "ID") (pinfunction "ID_ID") (pintype "bidirectional"))
    )
    (net (code "141") (name "unconnected-(U6-R1IN-Pad4)") (class "Default")
      (node (ref "U6") (pin "4") (pinfunction "R1IN_4") (pintype "input"))
    )
    (net (code "142") (name "unconnected-(U6-R1OUT-Pad3)") (class "Default")
      (node (ref "U6") (pin "3") (pinfunction "R1OUT_3") (pintype "output"))
    )
    (net (code "143") (name "unconnected-(U6-T1IN-Pad2)") (class "Default")
      (node (ref "U6") (pin "2") (pinfunction "T1IN_2") (pintype "input"))
    )
    (net (code "144") (name "unconnected-(U6-T1OUT-Pad5)") (class "Default")
      (node (ref "U6") (pin "5") (pinfunction "T1OUT_5") (pintype "output"))
    )
  )
)
